# CAN.net
KiCad netlist of a schematic drawn in Altium Designer
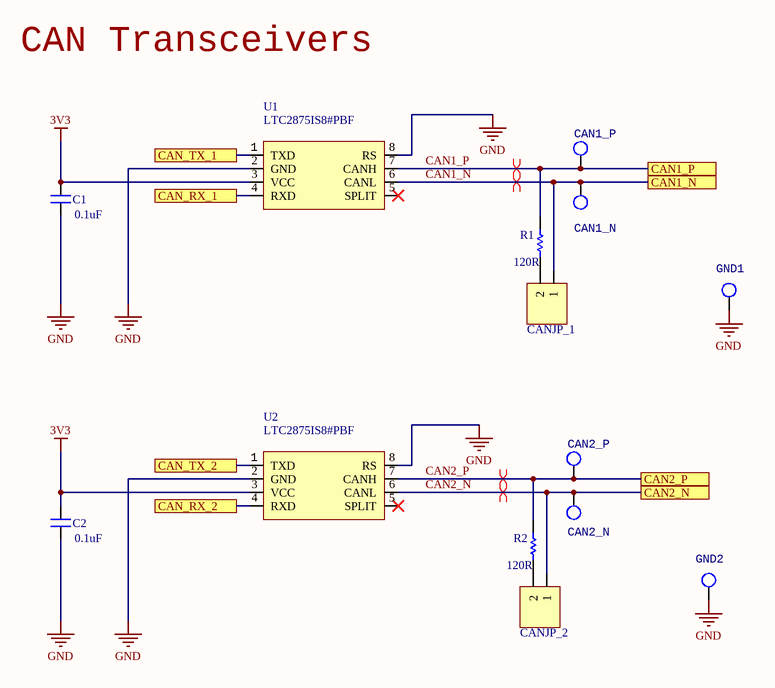
[diagram p0: CAN.SchDoc]

(export (version "E")
  (design (tool "Eeschema 10.0.6"))
  (components
    (comp (ref "C1")
      (value "0.1uF")
      (footprint "CAPC0603(1608)55_N")
      (description "CAP CER 0.1UF 16V X7R 0603")
      (fields (field (name "MPN") "CC0603KRX7R7BB104") (field (name "MANUFACTURER") "Yageo"))
      (libsource (lib "UWRT_Schematic_Library_2020") (part "CAP_0.1uF_16V_0603"))
    )
    (comp (ref "C2")
      (value "0.1uF")
      (footprint "CAPC0603(1608)55_N")
      (description "CAP CER 0.1UF 16V X7R 0603")
      (fields (field (name "MPN") "CC0603KRX7R7BB104") (field (name "MANUFACTURER") "Yageo"))
      (libsource (lib "UWRT_Schematic_Library_2020") (part "CAP_0.1uF_16V_0603"))
    )
    (comp (ref "CAN1_N")
      (value "TESTPOINT_LOOP")
      (footprint "TESTPOINT_LOOP")
      (description "Loop testpoint through-hole pad")
      (fields (field (name "MANUFACTURER") "Keystone Electronics"))
      (libsource (lib "UWRT_Schematic_Library_2020") (part "TESTPOINT_LOOP"))
    )
    (comp (ref "CAN1_P")
      (value "TESTPOINT_LOOP")
      (footprint "TESTPOINT_LOOP")
      (description "Loop testpoint through-hole pad")
      (fields (field (name "MANUFACTURER") "Keystone Electronics"))
      (libsource (lib "UWRT_Schematic_Library_2020") (part "TESTPOINT_LOOP"))
    )
    (comp (ref "CAN2_N")
      (value "TESTPOINT_LOOP")
      (footprint "TESTPOINT_LOOP")
      (description "Loop testpoint through-hole pad")
      (fields (field (name "MANUFACTURER") "Keystone Electronics"))
      (libsource (lib "UWRT_Schematic_Library_2020") (part "TESTPOINT_LOOP"))
    )
    (comp (ref "CAN2_P")
      (value "TESTPOINT_LOOP")
      (footprint "TESTPOINT_LOOP")
      (description "Loop testpoint through-hole pad")
      (fields (field (name "MANUFACTURER") "Keystone Electronics"))
      (libsource (lib "UWRT_Schematic_Library_2020") (part "TESTPOINT_LOOP"))
    )
    (comp (ref "CANJP_1")
      (value "JUMPER_2")
      (footprint "HDR1X2")
      (description "HEADER 2X1")
      (libsource (lib "UWRT_Schematic_Library_2020") (part "JUMPER_2"))
    )
    (comp (ref "CANJP_2")
      (value "JUMPER_2")
      (footprint "HDR1X2")
      (description "HEADER 2X1")
      (libsource (lib "UWRT_Schematic_Library_2020") (part "JUMPER_2"))
    )
    (comp (ref "GND1")
      (value "TESTPOINT_LOOP")
      (footprint "TESTPOINT_LOOP")
      (description "Loop testpoint through-hole pad")
      (fields (field (name "MANUFACTURER") "Keystone Electronics"))
      (libsource (lib "UWRT_Schematic_Library_2020") (part "TESTPOINT_LOOP"))
    )
    (comp (ref "GND2")
      (value "TESTPOINT_LOOP")
      (footprint "TESTPOINT_LOOP")
      (description "Loop testpoint through-hole pad")
      (fields (field (name "MANUFACTURER") "Keystone Electronics"))
      (libsource (lib "UWRT_Schematic_Library_2020") (part "TESTPOINT_LOOP"))
    )
    (comp (ref "R1")
      (value "120R")
      (footprint "RESC0603(1608)_N")
      (description "RES SMD 120 OHM 5% 1/10W 0603")
      (fields (field (name "MANUFACTURER") "Yageo") (field (name "MPN") "RC0603JR-07120RL"))
      (libsource (lib "UWRT_Schematic_Library_2020") (part "RES_120R_0603"))
    )
    (comp (ref "R2")
      (value "120R")
      (footprint "RESC0603(1608)_N")
      (description "RES SMD 120 OHM 5% 1/10W 0603")
      (fields (field (name "MANUFACTURER") "Yageo") (field (name "MPN") "RC0603JR-07120RL"))
      (libsource (lib "UWRT_Schematic_Library_2020") (part "RES_120R_0603"))
    )
    (comp (ref "U1")
      (value "IC TXRX CAN")
      (footprint "LT-S8_N")
      (description "IC TXRX CAN 4MBPS 8SO")
      (fields (field (name "MANUFACTURER") "Linear Technologies") (field (name "MPN") "LTC2875IS8#PBF"))
      (libsource (lib "UWRT_Schematic_Library_2020") (part "LTC2875"))
    )
    (comp (ref "U2")
      (value "IC TXRX CAN")
      (footprint "LT-S8_N")
      (description "IC TXRX CAN 4MBPS 8SO")
      (fields (field (name "MANUFACTURER") "Linear Technologies") (field (name "MPN") "LTC2875IS8#PBF"))
      (libsource (lib "UWRT_Schematic_Library_2020") (part "LTC2875"))
    )
  )
  (nets
    (net (code "1") (name "/CAN1_N") (class "Default")
      (node (ref "CAN1_N") (pin "1") (pintype "passive"))
      (node (ref "CANJP_1") (pin "1") (pinfunction "1_1") (pintype "passive"))
      (node (ref "U1") (pin "6") (pinfunction "CANL_6") (pintype "passive"))
    )
    (net (code "2") (name "/CAN1_P") (class "Default")
      (node (ref "CAN1_P") (pin "1") (pintype "passive"))
      (node (ref "R1") (pin "1") (pinfunction "1_1") (pintype "passive"))
      (node (ref "U1") (pin "7") (pinfunction "CANH_7") (pintype "passive"))
    )
    (net (code "3") (name "/CAN2_N") (class "Default")
      (node (ref "CAN2_N") (pin "1") (pintype "passive"))
      (node (ref "CANJP_2") (pin "1") (pinfunction "1_1") (pintype "passive"))
      (node (ref "U2") (pin "6") (pinfunction "CANL_6") (pintype "passive"))
    )
    (net (code "4") (name "/CAN2_P") (class "Default")
      (node (ref "CAN2_P") (pin "1") (pintype "passive"))
      (node (ref "R2") (pin "1") (pinfunction "1_1") (pintype "passive"))
      (node (ref "U2") (pin "7") (pinfunction "CANH_7") (pintype "passive"))
    )
    (net (code "5") (name "/CAN_RX_1") (class "Default")
      (node (ref "U1") (pin "4") (pinfunction "RXD_4") (pintype "passive"))
    )
    (net (code "6") (name "/CAN_RX_2") (class "Default")
      (node (ref "U2") (pin "4") (pinfunction "RXD_4") (pintype "passive"))
    )
    (net (code "7") (name "/CAN_TX_1") (class "Default")
      (node (ref "U1") (pin "1") (pinfunction "TXD_1") (pintype "passive"))
    )
    (net (code "8") (name "/CAN_TX_2") (class "Default")
      (node (ref "U2") (pin "1") (pinfunction "TXD_1") (pintype "passive"))
    )
    (net (code "9") (name "3V3") (class "Default")
      (node (ref "C1") (pin "2") (pinfunction "2_2") (pintype "passive"))
      (node (ref "C2") (pin "2") (pinfunction "2_2") (pintype "passive"))
      (node (ref "U1") (pin "3") (pinfunction "VCC_3") (pintype "passive"))
      (node (ref "U2") (pin "3") (pinfunction "VCC_3") (pintype "passive"))
    )
    (net (code "10") (name "GND") (class "Default")
      (node (ref "C1") (pin "1") (pinfunction "1_1") (pintype "passive"))
      (node (ref "C2") (pin "1") (pinfunction "1_1") (pintype "passive"))
      (node (ref "GND1") (pin "1") (pintype "passive"))
      (node (ref "GND2") (pin "1") (pintype "passive"))
      (node (ref "U1") (pin "2") (pinfunction "GND_2") (pintype "passive"))
      (node (ref "U1") (pin "8") (pinfunction "RS_8") (pintype "passive"))
      (node (ref "U2") (pin "2") (pinfunction "GND_2") (pintype "passive"))
      (node (ref "U2") (pin "8") (pinfunction "RS_8") (pintype "passive"))
    )
    (net (code "11") (name "Net-(CANJP_1-Pad2)") (class "Default")
      (node (ref "CANJP_1") (pin "2") (pinfunction "2_2") (pintype "passive"))
      (node (ref "R1") (pin "2") (pinfunction "2_2") (pintype "passive"))
    )
    (net (code "12") (name "Net-(CANJP_2-Pad2)") (class "Default")
      (node (ref "CANJP_2") (pin "2") (pinfunction "2_2") (pintype "passive"))
      (node (ref "R2") (pin "2") (pinfunction "2_2") (pintype "passive"))
    )
    (net (code "13") (name "unconnected-(U1-SPLIT-Pad5)") (class "Default")
      (node (ref "U1") (pin "5") (pinfunction "SPLIT_5") (pintype "passive+no_connect"))
    )
    (net (code "14") (name "unconnected-(U2-SPLIT-Pad5)") (class "Default")
      (node (ref "U2") (pin "5") (pinfunction "SPLIT_5") (pintype "passive+no_connect"))
    )
  )
)
